# Lux_5V_Compatable.net
KiCad netlist of a schematic drawn in EAGLE
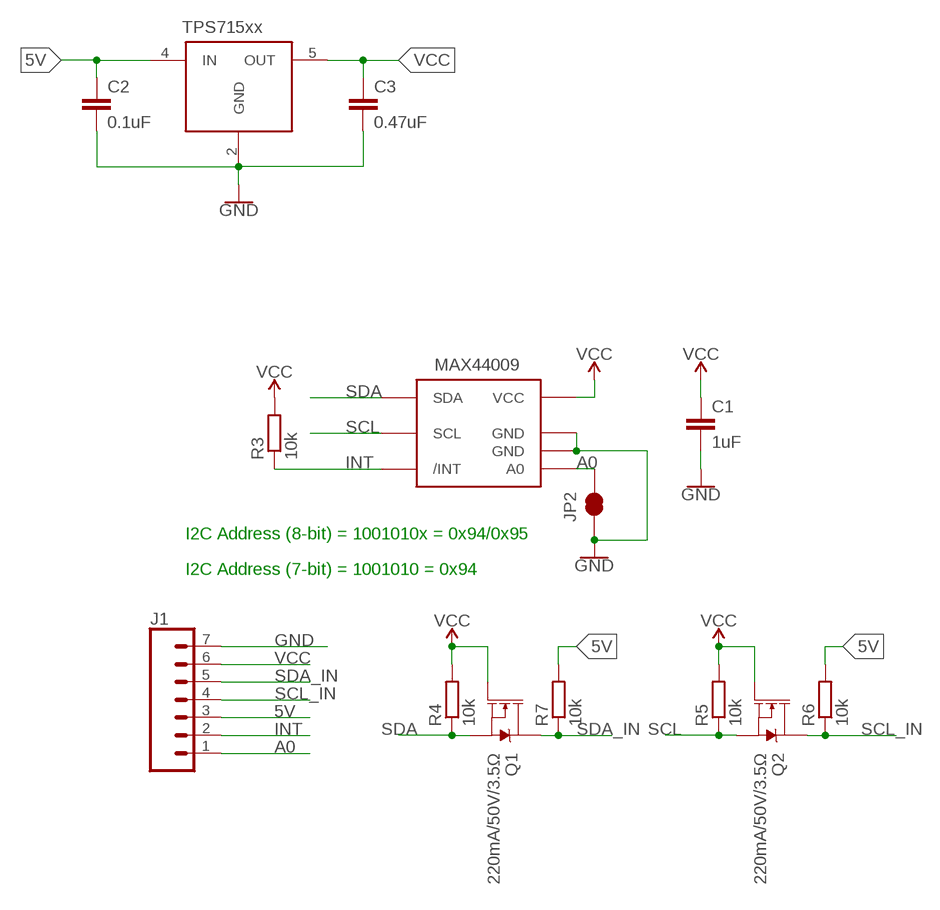
[diagram p0: schematic, sheet 1]

(export (version "E")
  (design (tool "Eeschema 10.0.6"))
  (components
    (comp (ref "C1")
      (value "1uF")
      (footprint "eagle-import:C0603")
      (libsource (lib "eagle-import") (part "C-EUC0603"))
    )
    (comp (ref "C2")
      (value "0.1uF")
      (footprint "eagle-import:C0603")
      (libsource (lib "eagle-import") (part "C-EUC0603"))
    )
    (comp (ref "C3")
      (value "0.47uF")
      (footprint "eagle-import:C0603")
      (libsource (lib "eagle-import") (part "C-EUC0603"))
    )
    (comp (ref "J1")
      (value "CONN_07")
      (footprint "eagle-import:1X07")
      (libsource (lib "eagle-import") (part "CONN_07"))
    )
    (comp (ref "JP2")
      (value "JUMPER-SMT_2_NC_TRACE_SILK")
      (footprint "eagle-import:SMT-JUMPER_2_NC_TRACE_SILK")
      (libsource (lib "eagle-import") (part "JUMPER-SMT_2_NC_TRACE_SILK"))
    )
    (comp (ref "Q1")
      (value "220mA/50V/3.5Ω")
      (footprint "eagle-import:SOT23-3")
      (libsource (lib "eagle-import") (part "MOSFET-NCH-BSS138"))
    )
    (comp (ref "Q2")
      (value "220mA/50V/3.5Ω")
      (footprint "eagle-import:SOT23-3")
      (libsource (lib "eagle-import") (part "MOSFET-NCH-BSS138"))
    )
    (comp (ref "R3")
      (value "10k")
      (footprint "eagle-import:R0603")
      (libsource (lib "eagle-import") (part "R-EU_R0603"))
    )
    (comp (ref "R4")
      (value "10k")
      (footprint "eagle-import:R0603")
      (libsource (lib "eagle-import") (part "R-EU_R0603"))
    )
    (comp (ref "R5")
      (value "10k")
      (footprint "eagle-import:R0603")
      (libsource (lib "eagle-import") (part "R-EU_R0603"))
    )
    (comp (ref "R6")
      (value "10k")
      (footprint "eagle-import:R0603")
      (libsource (lib "eagle-import") (part "R-EU_R0603"))
    )
    (comp (ref "R7")
      (value "10k")
      (footprint "eagle-import:R0603")
      (libsource (lib "eagle-import") (part "R-EU_R0603"))
    )
    (comp (ref "U$1")
      (value "MAX44009")
      (footprint "eagle-import:UTDFN6")
      (libsource (lib "eagle-import") (part "MAX44009"))
    )
    (comp (ref "U$2")
      (value "TPS715XX")
      (footprint "eagle-import:DCK_R-PDSO-G5")
      (libsource (lib "eagle-import") (part "TPS715XX"))
    )
  )
  (nets
    (net (code "1") (name "/A0") (class "Default")
      (node (ref "J1") (pin "1") (pinfunction "1_1") (pintype "passive"))
      (node (ref "JP2") (pin "2") (pinfunction "2_2") (pintype "passive"))
      (node (ref "U$1") (pin "P$3") (pinfunction "A0_P$3") (pintype "input"))
    )
    (net (code "2") (name "/INT") (class "Default")
      (node (ref "J1") (pin "2") (pinfunction "2_2") (pintype "passive"))
      (node (ref "R3") (pin "1") (pinfunction "1_1") (pintype "passive"))
      (node (ref "U$1") (pin "P$4") (pinfunction "/INT_P$4") (pintype "output"))
    )
    (net (code "3") (name "/SCL") (class "Default")
      (node (ref "Q2") (pin "2") (pinfunction "S_2") (pintype "bidirectional"))
      (node (ref "R5") (pin "1") (pinfunction "1_1") (pintype "passive"))
      (node (ref "U$1") (pin "P$5") (pinfunction "SCL_P$5") (pintype "bidirectional"))
    )
    (net (code "4") (name "/SCL_IN") (class "Default")
      (node (ref "J1") (pin "4") (pinfunction "4_4") (pintype "passive"))
      (node (ref "Q2") (pin "3") (pinfunction "D_3") (pintype "bidirectional"))
      (node (ref "R6") (pin "1") (pinfunction "1_1") (pintype "passive"))
    )
    (net (code "5") (name "/SDA") (class "Default")
      (node (ref "Q1") (pin "2") (pinfunction "S_2") (pintype "bidirectional"))
      (node (ref "R4") (pin "1") (pinfunction "1_1") (pintype "passive"))
      (node (ref "U$1") (pin "P$6") (pinfunction "SDA_P$6") (pintype "bidirectional"))
    )
    (net (code "6") (name "/SDA_IN") (class "Default")
      (node (ref "J1") (pin "5") (pinfunction "5_5") (pintype "passive"))
      (node (ref "Q1") (pin "3") (pinfunction "D_3") (pintype "bidirectional"))
      (node (ref "R7") (pin "1") (pinfunction "1_1") (pintype "passive"))
    )
    (net (code "7") (name "5V") (class "Default")
      (node (ref "C2") (pin "1") (pinfunction "1_1") (pintype "passive"))
      (node (ref "J1") (pin "3") (pinfunction "3_3") (pintype "passive"))
      (node (ref "R6") (pin "2") (pinfunction "2_2") (pintype "passive"))
      (node (ref "R7") (pin "2") (pinfunction "2_2") (pintype "passive"))
      (node (ref "U$2") (pin "4") (pinfunction "IN_4") (pintype "power_in"))
    )
    (net (code "8") (name "GND") (class "Default")
      (node (ref "C1") (pin "2") (pinfunction "2_2") (pintype "passive"))
      (node (ref "C2") (pin "2") (pinfunction "2_2") (pintype "passive"))
      (node (ref "C3") (pin "2") (pinfunction "2_2") (pintype "passive"))
      (node (ref "J1") (pin "7") (pinfunction "7_7") (pintype "passive"))
      (node (ref "JP2") (pin "1") (pinfunction "1_1") (pintype "passive"))
      (node (ref "U$1") (pin "P$2") (pinfunction "GND_P$2") (pintype "power_in"))
      (node (ref "U$1") (pin "P$7") (pinfunction "GND_P$7") (pintype "bidirectional"))
      (node (ref "U$2") (pin "2") (pinfunction "GND_2") (pintype "power_in"))
    )
    (net (code "9") (name "VCC") (class "Default")
      (node (ref "C1") (pin "1") (pinfunction "1_1") (pintype "passive"))
      (node (ref "C3") (pin "1") (pinfunction "1_1") (pintype "passive"))
      (node (ref "J1") (pin "6") (pinfunction "6_6") (pintype "passive"))
      (node (ref "Q1") (pin "1") (pinfunction "G_1") (pintype "bidirectional"))
      (node (ref "Q2") (pin "1") (pinfunction "G_1") (pintype "bidirectional"))
      (node (ref "R3") (pin "2") (pinfunction "2_2") (pintype "passive"))
      (node (ref "R4") (pin "2") (pinfunction "2_2") (pintype "passive"))
      (node (ref "R5") (pin "2") (pinfunction "2_2") (pintype "passive"))
      (node (ref "U$1") (pin "P$1") (pinfunction "VCC_P$1") (pintype "power_in"))
      (node (ref "U$2") (pin "5") (pinfunction "OUT_5") (pintype "power_in"))
    )
  )
)
